# RTC.net
KiCad netlist of a schematic drawn in Altium Designer
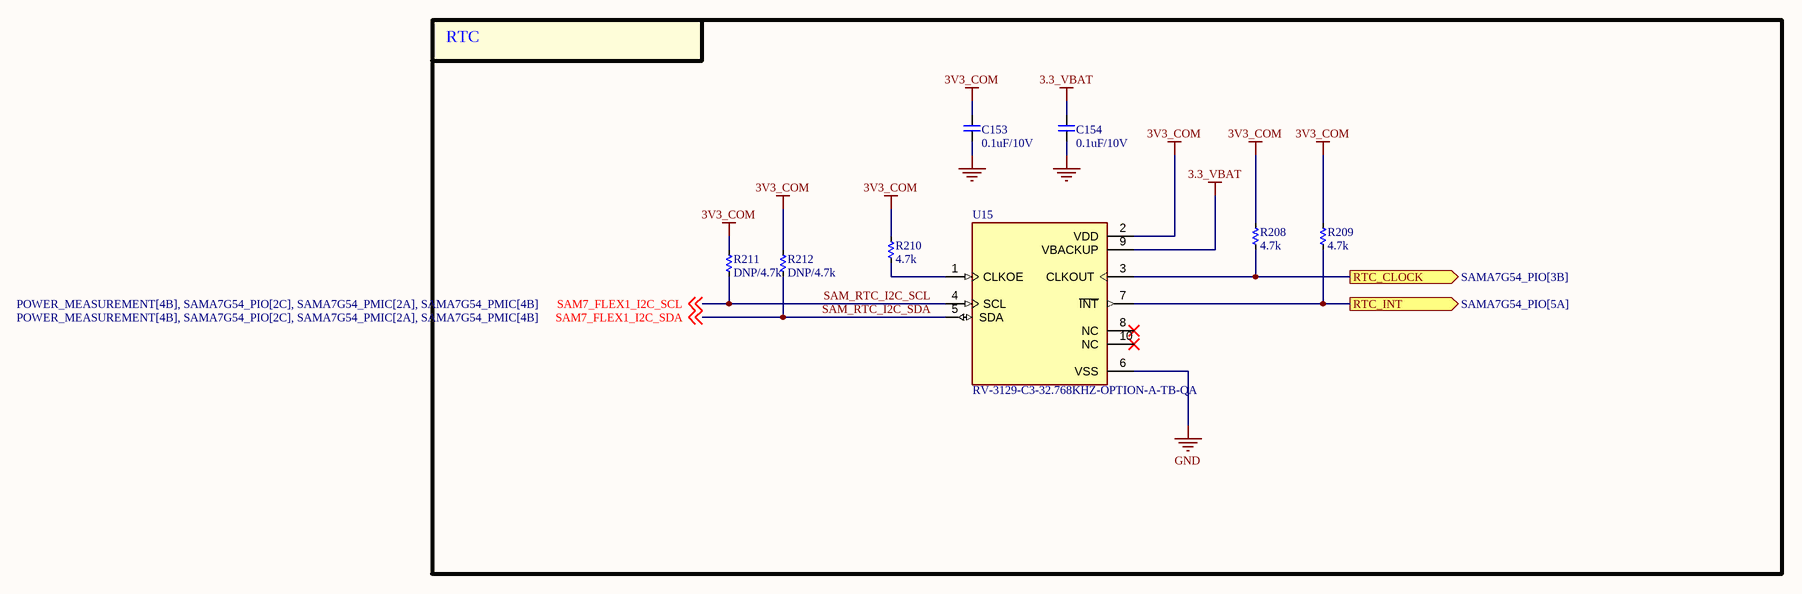
[diagram p0: RTC.SchDoc]

(export (version "E")
  (design (tool "Eeschema 10.0.6"))
  (components
    (comp (ref "C153")
      (value "0.1uF/10V")
      (footprint "CAP_C_1005X50_L")
      (description "CAP")
      (libsource (lib "LABLIB") (part "_CAP_C_2"))
    )
    (comp (ref "C154")
      (value "0.1uF/10V")
      (footprint "CAP_C_1005X50_L")
      (description "CAP")
      (libsource (lib "LABLIB") (part "_CAP_C_2"))
    )
    (comp (ref "R208")
      (value "4.7k")
      (footprint "RES_C_1005x30_L")
      (description "RES")
      (libsource (lib "IFBschelib") (part "_RES_B_2"))
    )
    (comp (ref "R209")
      (value "4.7k")
      (footprint "RES_C_1005x30_L")
      (description "RES")
      (libsource (lib "IFBschelib") (part "_RES_B_2"))
    )
    (comp (ref "R210")
      (value "4.7k")
      (footprint "RES_C_1005x30_L")
      (description "RES")
      (libsource (lib "IFBschelib") (part "_RES_B_2"))
    )
    (comp (ref "R211")
      (value "DNP/4.7k")
      (footprint "RES_C_1005x30_L")
      (description "RES")
      (libsource (lib "IFBschelib") (part "_RES_B_2"))
    )
    (comp (ref "R212")
      (value "DNP/4.7k")
      (footprint "RES_C_1005x30_L")
      (description "RES")
      (libsource (lib "IFBschelib") (part "_RES_B_2"))
    )
    (comp (ref "U15")
      (value "RV-3129-C3-32.768KHZ-OPTION-A-TB-QA")
      (footprint "IC_RV-3129-C3-32.768KHZ-OPTION-A-TB-QA")
      (description "Real-Time Clock Module with I2C-Bus")
      (libsource (lib "IFBschelib") (part "RV-3129-C3-32.768KHZ-OPTION-A-TB-QA"))
    )
  )
  (nets
    (net (code "1") (name "/RTC_CLOCK") (class "Default")
      (node (ref "R208") (pin "2") (pinfunction "2_2") (pintype "passive"))
      (node (ref "U15") (pin "3") (pinfunction "CLKOUT_3") (pintype "passive"))
    )
    (net (code "2") (name "/RTC_INT") (class "Default")
      (node (ref "R209") (pin "2") (pinfunction "2_2") (pintype "passive"))
      (node (ref "U15") (pin "7") (pinfunction "~{INT}_7") (pintype "output"))
    )
    (net (code "3") (name "3.3_VBAT") (class "Default")
      (node (ref "C154") (pin "2") (pinfunction "2_2") (pintype "passive"))
      (node (ref "U15") (pin "9") (pinfunction "VBACKUP_9") (pintype "power_in"))
    )
    (net (code "4") (name "3V3_COM") (class "Default")
      (node (ref "C153") (pin "2") (pinfunction "2_2") (pintype "passive"))
      (node (ref "R208") (pin "1") (pinfunction "1_1") (pintype "passive"))
      (node (ref "R209") (pin "1") (pinfunction "1_1") (pintype "passive"))
      (node (ref "R210") (pin "1") (pinfunction "1_1") (pintype "passive"))
      (node (ref "R211") (pin "1") (pinfunction "1_1") (pintype "passive"))
      (node (ref "R212") (pin "1") (pinfunction "1_1") (pintype "passive"))
      (node (ref "U15") (pin "2") (pinfunction "VDD_2") (pintype "power_in"))
    )
    (net (code "5") (name "GND") (class "Default")
      (node (ref "C153") (pin "1") (pinfunction "1_1") (pintype "passive"))
      (node (ref "C154") (pin "1") (pinfunction "1_1") (pintype "passive"))
      (node (ref "U15") (pin "6") (pinfunction "VSS_6") (pintype "power_in"))
    )
    (net (code "6") (name "Net-(U15-CLKOE)") (class "Default")
      (node (ref "R210") (pin "2") (pinfunction "2_2") (pintype "passive"))
      (node (ref "U15") (pin "1") (pinfunction "CLKOE_1") (pintype "input"))
    )
    (net (code "7") (name "SAM7_FLEX1_I2C_SCL") (class "Default")
      (node (ref "R211") (pin "2") (pinfunction "2_2") (pintype "passive"))
      (node (ref "U15") (pin "4") (pinfunction "SCL_4") (pintype "input"))
    )
    (net (code "8") (name "SAM7_FLEX1_I2C_SDA") (class "Default")
      (node (ref "R212") (pin "2") (pinfunction "2_2") (pintype "passive"))
      (node (ref "U15") (pin "5") (pinfunction "SDA_5") (pintype "bidirectional"))
    )
    (net (code "9") (name "unconnected-(U15-NC-Pad8)") (class "Default")
      (node (ref "U15") (pin "8") (pinfunction "NC_8") (pintype "passive+no_connect"))
    )
    (net (code "10") (name "unconnected-(U15-NC-Pad10)") (class "Default")
      (node (ref "U15") (pin "10") (pinfunction "NC_10") (pintype "passive+no_connect"))
    )
  )
)
